# Data_Conversion.net
KiCad netlist of a schematic drawn in Altium Designer
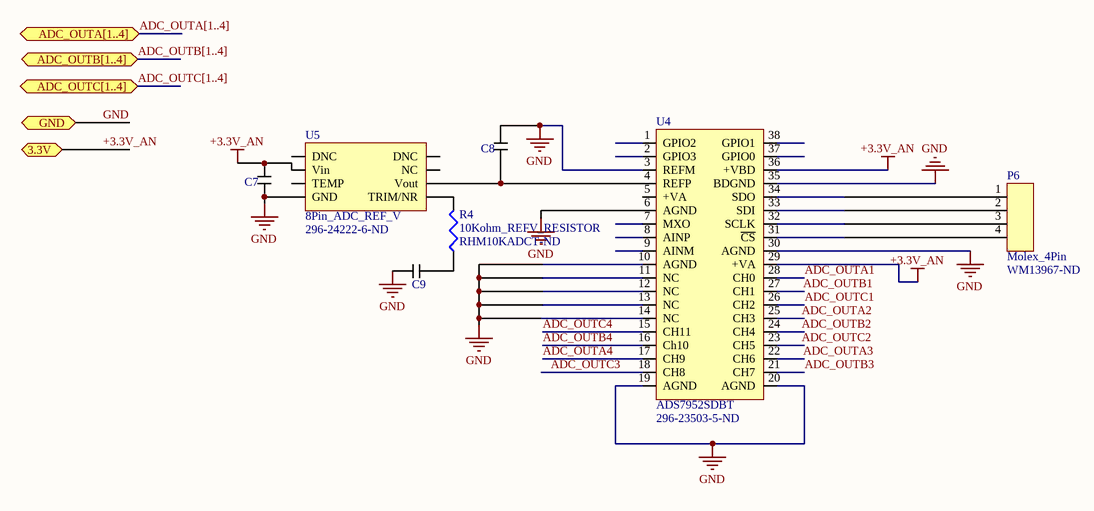
[diagram p0: Data_Conversion.SchDoc]

(export (version "E")
  (design (tool "Eeschema 10.0.6"))
  (components
    (comp (ref "C7")
      (value "0.1uF Cap")
      (footprint "0.1uF_Kemet")
      (description "C0603C101K8GAC7867 Kemet Capacitor")
      (libsource (lib "Thermistor_Expansion_Board") (part "0.1uF Cap"))
    )
    (comp (ref "C8")
      (value "0.1uF Cap")
      (footprint "0.1uF_Kemet")
      (description "C0603C101K8GAC7867 Kemet Capacitor")
      (libsource (lib "Thermistor_Expansion_Board") (part "0.1uF Cap"))
    )
    (comp (ref "C9")
      (value "0.1uF Cap")
      (footprint "0.1uF_Kemet")
      (description "C0603C101K8GAC7867 Kemet Capacitor")
      (libsource (lib "Thermistor_Expansion_Board") (part "0.1uF Cap"))
    )
    (comp (ref "P6")
      (value "Molex_4Pin")
      (footprint "MUX_SEL_CON")
      (fields (field (name "SUPPLIER PART NUMBER 1") "WM13967-ND"))
      (libsource (lib "Thermistor_Expansion_Board") (part "Component_1_2"))
    )
    (comp (ref "R4")
      (value "10Kohm_REFV_RESISTOR")
      (footprint "REFV_10K_RES")
      (fields
        (field (name "MANUFACTURER") "Rohm")
        (field (name "MANUFACTURER PART NUMBER") "ESR03EZPF1002")
        (field (name "TOLERANCE") "1%")
        (field (name "SUPPLIER PART NUMBER 1") "RHM10KADCT-ND")
      )
      (libsource (lib "Thermistor_Expansion_Board") (part "10Kohm_REFV_RESISTOR"))
    )
    (comp (ref "U4")
      (value "ADS7952SDBT")
      (footprint "TSSOP50P640X120-38N")
      (fields (field (name "SUPPLIER PART NUMBER 1") "296-23503-5-ND"))
      (libsource (lib "TI_ADC_38TSSOP") (part "ADS7952SDBT"))
    )
    (comp (ref "U5")
      (value "8Pin_ADC_REF_V")
      (footprint "SOIC127P600X175-8N")
      (fields
        (field (name "MANUFACTURER") "Texas Instruments")
        (field (name "MANUFACTURER PART NUMBER") "REF5025AQDRQ1")
        (field (name "TOLERANCE") "0.1%")
        (field (name "SUPPLIER PART NUMBER 1") "296-24222-6-ND")
      )
      (libsource (lib "Thermistor_Expansion_Board") (part "8Pin_ADC_REF_V"))
    )
  )
  (nets
    (net (code "1") (name "+3.3V_AN") (class "Default")
      (node (ref "C7") (pin "2") (pinfunction "2_2") (pintype "passive"))
      (node (ref "U4") (pin "29") (pinfunction "+VA_29") (pintype "passive"))
      (node (ref "U4") (pin "36") (pinfunction "+VBD_36") (pintype "passive"))
      (node (ref "U5") (pin "2") (pinfunction "Vin_2") (pintype "passive"))
    )
    (net (code "2") (name "/ADC_OUTA1") (class "Default")
      (node (ref "U4") (pin "28") (pinfunction "CH0_28") (pintype "passive"))
    )
    (net (code "3") (name "/ADC_OUTA2") (class "Default")
      (node (ref "U4") (pin "25") (pinfunction "CH3_25") (pintype "passive"))
    )
    (net (code "4") (name "/ADC_OUTA3") (class "Default")
      (node (ref "U4") (pin "22") (pinfunction "CH6_22") (pintype "passive"))
    )
    (net (code "5") (name "/ADC_OUTA4") (class "Default")
      (node (ref "U4") (pin "17") (pinfunction "CH9_17") (pintype "passive"))
    )
    (net (code "7") (name "/ADC_OUTB1") (class "Default")
      (node (ref "U4") (pin "27") (pinfunction "CH1_27") (pintype "passive"))
    )
    (net (code "8") (name "/ADC_OUTB2") (class "Default")
      (node (ref "U4") (pin "24") (pinfunction "CH4_24") (pintype "passive"))
    )
    (net (code "9") (name "/ADC_OUTB3") (class "Default")
      (node (ref "U4") (pin "21") (pinfunction "CH7_21") (pintype "passive"))
    )
    (net (code "10") (name "/ADC_OUTB4") (class "Default")
      (node (ref "U4") (pin "16") (pinfunction "Ch10_16") (pintype "passive"))
    )
    (net (code "12") (name "/ADC_OUTC1") (class "Default")
      (node (ref "U4") (pin "26") (pinfunction "CH2_26") (pintype "passive"))
    )
    (net (code "13") (name "/ADC_OUTC2") (class "Default")
      (node (ref "U4") (pin "23") (pinfunction "CH5_23") (pintype "passive"))
    )
    (net (code "14") (name "/ADC_OUTC3") (class "Default")
      (node (ref "U4") (pin "18") (pinfunction "CH8_18") (pintype "passive"))
    )
    (net (code "15") (name "/ADC_OUTC4") (class "Default")
      (node (ref "U4") (pin "15") (pinfunction "CH11_15") (pintype "passive"))
    )
    (net (code "17") (name "GND") (class "Default")
      (node (ref "C7") (pin "1") (pinfunction "1_1") (pintype "passive"))
      (node (ref "C8") (pin "2") (pinfunction "2_2") (pintype "passive"))
      (node (ref "C9") (pin "2") (pinfunction "2_2") (pintype "passive"))
      (node (ref "U4") (pin "10") (pinfunction "AGND_10") (pintype "passive"))
      (node (ref "U4") (pin "11") (pinfunction "NC_11") (pintype "passive"))
      (node (ref "U4") (pin "12") (pinfunction "NC_12") (pintype "passive"))
      (node (ref "U4") (pin "13") (pinfunction "NC_13") (pintype "passive"))
      (node (ref "U4") (pin "14") (pinfunction "NC_14") (pintype "passive"))
      (node (ref "U4") (pin "19") (pinfunction "AGND_19") (pintype "passive"))
      (node (ref "U4") (pin "20") (pinfunction "AGND_20") (pintype "passive"))
      (node (ref "U4") (pin "3") (pinfunction "REFM_3") (pintype "passive"))
      (node (ref "U4") (pin "30") (pinfunction "AGND_30") (pintype "passive"))
      (node (ref "U4") (pin "35") (pinfunction "BDGND_35") (pintype "passive"))
      (node (ref "U4") (pin "6") (pinfunction "AGND_6") (pintype "passive"))
      (node (ref "U5") (pin "4") (pinfunction "GND_4") (pintype "passive"))
    )
    (net (code "18") (name "Net-(R4-1)") (class "Default")
      (node (ref "C9") (pin "1") (pinfunction "1_1") (pintype "passive"))
      (node (ref "R4") (pin "4-1") (pinfunction "1_4-1") (pintype "passive"))
    )
    (net (code "19") (name "Net-(R4-2)") (class "Default")
      (node (ref "R4") (pin "4-2") (pinfunction "2_4-2") (pintype "passive"))
      (node (ref "U5") (pin "5") (pinfunction "TRIM/NR_5") (pintype "passive"))
    )
    (net (code "20") (name "Net-(U4-REFP)") (class "Default")
      (node (ref "C8") (pin "1") (pinfunction "1_1") (pintype "passive"))
      (node (ref "U4") (pin "4") (pinfunction "REFP_4") (pintype "passive"))
      (node (ref "U5") (pin "6") (pinfunction "Vout_6") (pintype "passive"))
    )
    (net (code "21") (name "Net-(U4-SCLK)") (class "Default")
      (node (ref "P6") (pin "3") (pintype "passive"))
      (node (ref "U4") (pin "32") (pinfunction "SCLK_32") (pintype "passive"))
    )
    (net (code "22") (name "Net-(U4-SDI)") (class "Default")
      (node (ref "P6") (pin "2") (pintype "passive"))
      (node (ref "U4") (pin "33") (pinfunction "SDI_33") (pintype "passive"))
    )
    (net (code "23") (name "Net-(U4-SDO)") (class "Default")
      (node (ref "P6") (pin "1") (pintype "passive"))
      (node (ref "U4") (pin "34") (pinfunction "SDO_34") (pintype "passive"))
    )
    (net (code "24") (name "Net-(U4-~{CS})") (class "Default")
      (node (ref "P6") (pin "4") (pintype "passive"))
      (node (ref "U4") (pin "31") (pinfunction "~{CS}_31") (pintype "passive"))
    )
    (net (code "25") (name "unconnected-(U4-+VA-Pad5)") (class "Default")
      (node (ref "U4") (pin "5") (pinfunction "+VA_5") (pintype "passive"))
    )
    (net (code "26") (name "unconnected-(U4-AINM-Pad9)") (class "Default")
      (node (ref "U4") (pin "9") (pinfunction "AINM_9") (pintype "passive"))
    )
    (net (code "27") (name "unconnected-(U4-AINP-Pad8)") (class "Default")
      (node (ref "U4") (pin "8") (pinfunction "AINP_8") (pintype "passive"))
    )
    (net (code "28") (name "unconnected-(U4-GPIO0-Pad37)") (class "Default")
      (node (ref "U4") (pin "37") (pinfunction "GPIO0_37") (pintype "passive"))
    )
    (net (code "29") (name "unconnected-(U4-GPIO1-Pad38)") (class "Default")
      (node (ref "U4") (pin "38") (pinfunction "GPIO1_38") (pintype "passive"))
    )
    (net (code "30") (name "unconnected-(U4-GPIO2-Pad1)") (class "Default")
      (node (ref "U4") (pin "1") (pinfunction "GPIO2_1") (pintype "passive"))
    )
    (net (code "31") (name "unconnected-(U4-GPIO3-Pad2)") (class "Default")
      (node (ref "U4") (pin "2") (pinfunction "GPIO3_2") (pintype "passive"))
    )
    (net (code "32") (name "unconnected-(U4-MXO-Pad7)") (class "Default")
      (node (ref "U4") (pin "7") (pinfunction "MXO_7") (pintype "passive"))
    )
    (net (code "33") (name "unconnected-(U5-DNC-Pad1)") (class "Default")
      (node (ref "U5") (pin "1") (pinfunction "DNC_1") (pintype "passive"))
    )
    (net (code "34") (name "unconnected-(U5-DNC-Pad8)") (class "Default")
      (node (ref "U5") (pin "8") (pinfunction "DNC_8") (pintype "passive"))
    )
    (net (code "35") (name "unconnected-(U5-NC-Pad7)") (class "Default")
      (node (ref "U5") (pin "7") (pinfunction "NC_7") (pintype "passive"))
    )
    (net (code "36") (name "unconnected-(U5-TEMP-Pad3)") (class "Default")
      (node (ref "U5") (pin "3") (pinfunction "TEMP_3") (pintype "passive"))
    )
  )
)
